# Power_Supply.net
KiCad netlist of a schematic drawn in Altium Designer
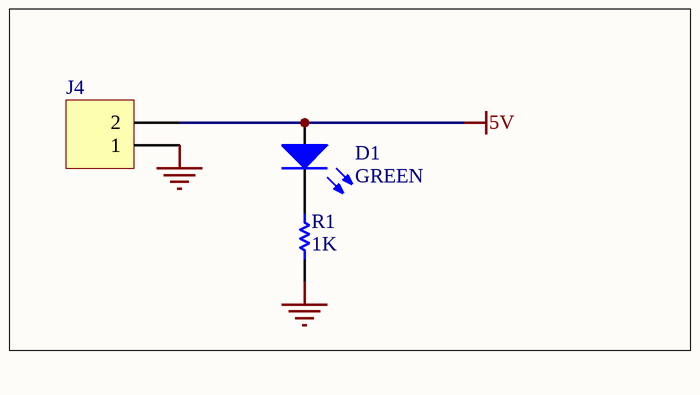
[diagram p0: Power Supply.SchDoc]

(export (version "E")
  (design (tool "Eeschema 10.0.6"))
  (components
    (comp (ref "D1")
      (value "GREEN")
      (footprint "LED-5mm_Red")
      (description "Typical INFRARED GaAs LED")
      (fields (field (name "MANUFACTURER") "Generic Components") (field (name "PUBLISHER") "Altium Limited"))
      (libsource (lib "Miscellaneous Devices") (part "LED"))
    )
    (comp (ref "J4")
      (value "2PIN")
      (footprint "HDR1X2")
      (description "Header, 2-Pin")
      (fields (field (name "MANUFACTURER") "Generic Components") (field (name "PUBLISHER") "Altium Limited"))
      (libsource (lib "Miscellaneous Connectors") (part "Header 2"))
    )
    (comp (ref "R1")
      (value "1K")
      (footprint "0805")
      (description "Resistor")
      (fields (field (name "PUBLISHER") "Altium Limited"))
      (libsource (lib "Miscellaneous Devices") (part "Res1"))
    )
  )
  (nets
    (net (code "1") (name "5V") (class "Default")
      (node (ref "D1") (pin "1") (pinfunction "A_1") (pintype "passive"))
      (node (ref "J4") (pin "2") (pinfunction "2_2") (pintype "passive"))
    )
    (net (code "2") (name "GND") (class "Default")
      (node (ref "J4") (pin "1") (pinfunction "1_1") (pintype "passive"))
      (node (ref "R1") (pin "2") (pinfunction "2_2") (pintype "passive"))
    )
    (net (code "3") (name "Net-(D1-K)") (class "Default")
      (node (ref "D1") (pin "2") (pinfunction "K_2") (pintype "passive"))
      (node (ref "R1") (pin "1") (pinfunction "1_1") (pintype "passive"))
    )
  )
)
